# schematic.net
KiCad netlist of a schematic drawn in EasyEDA
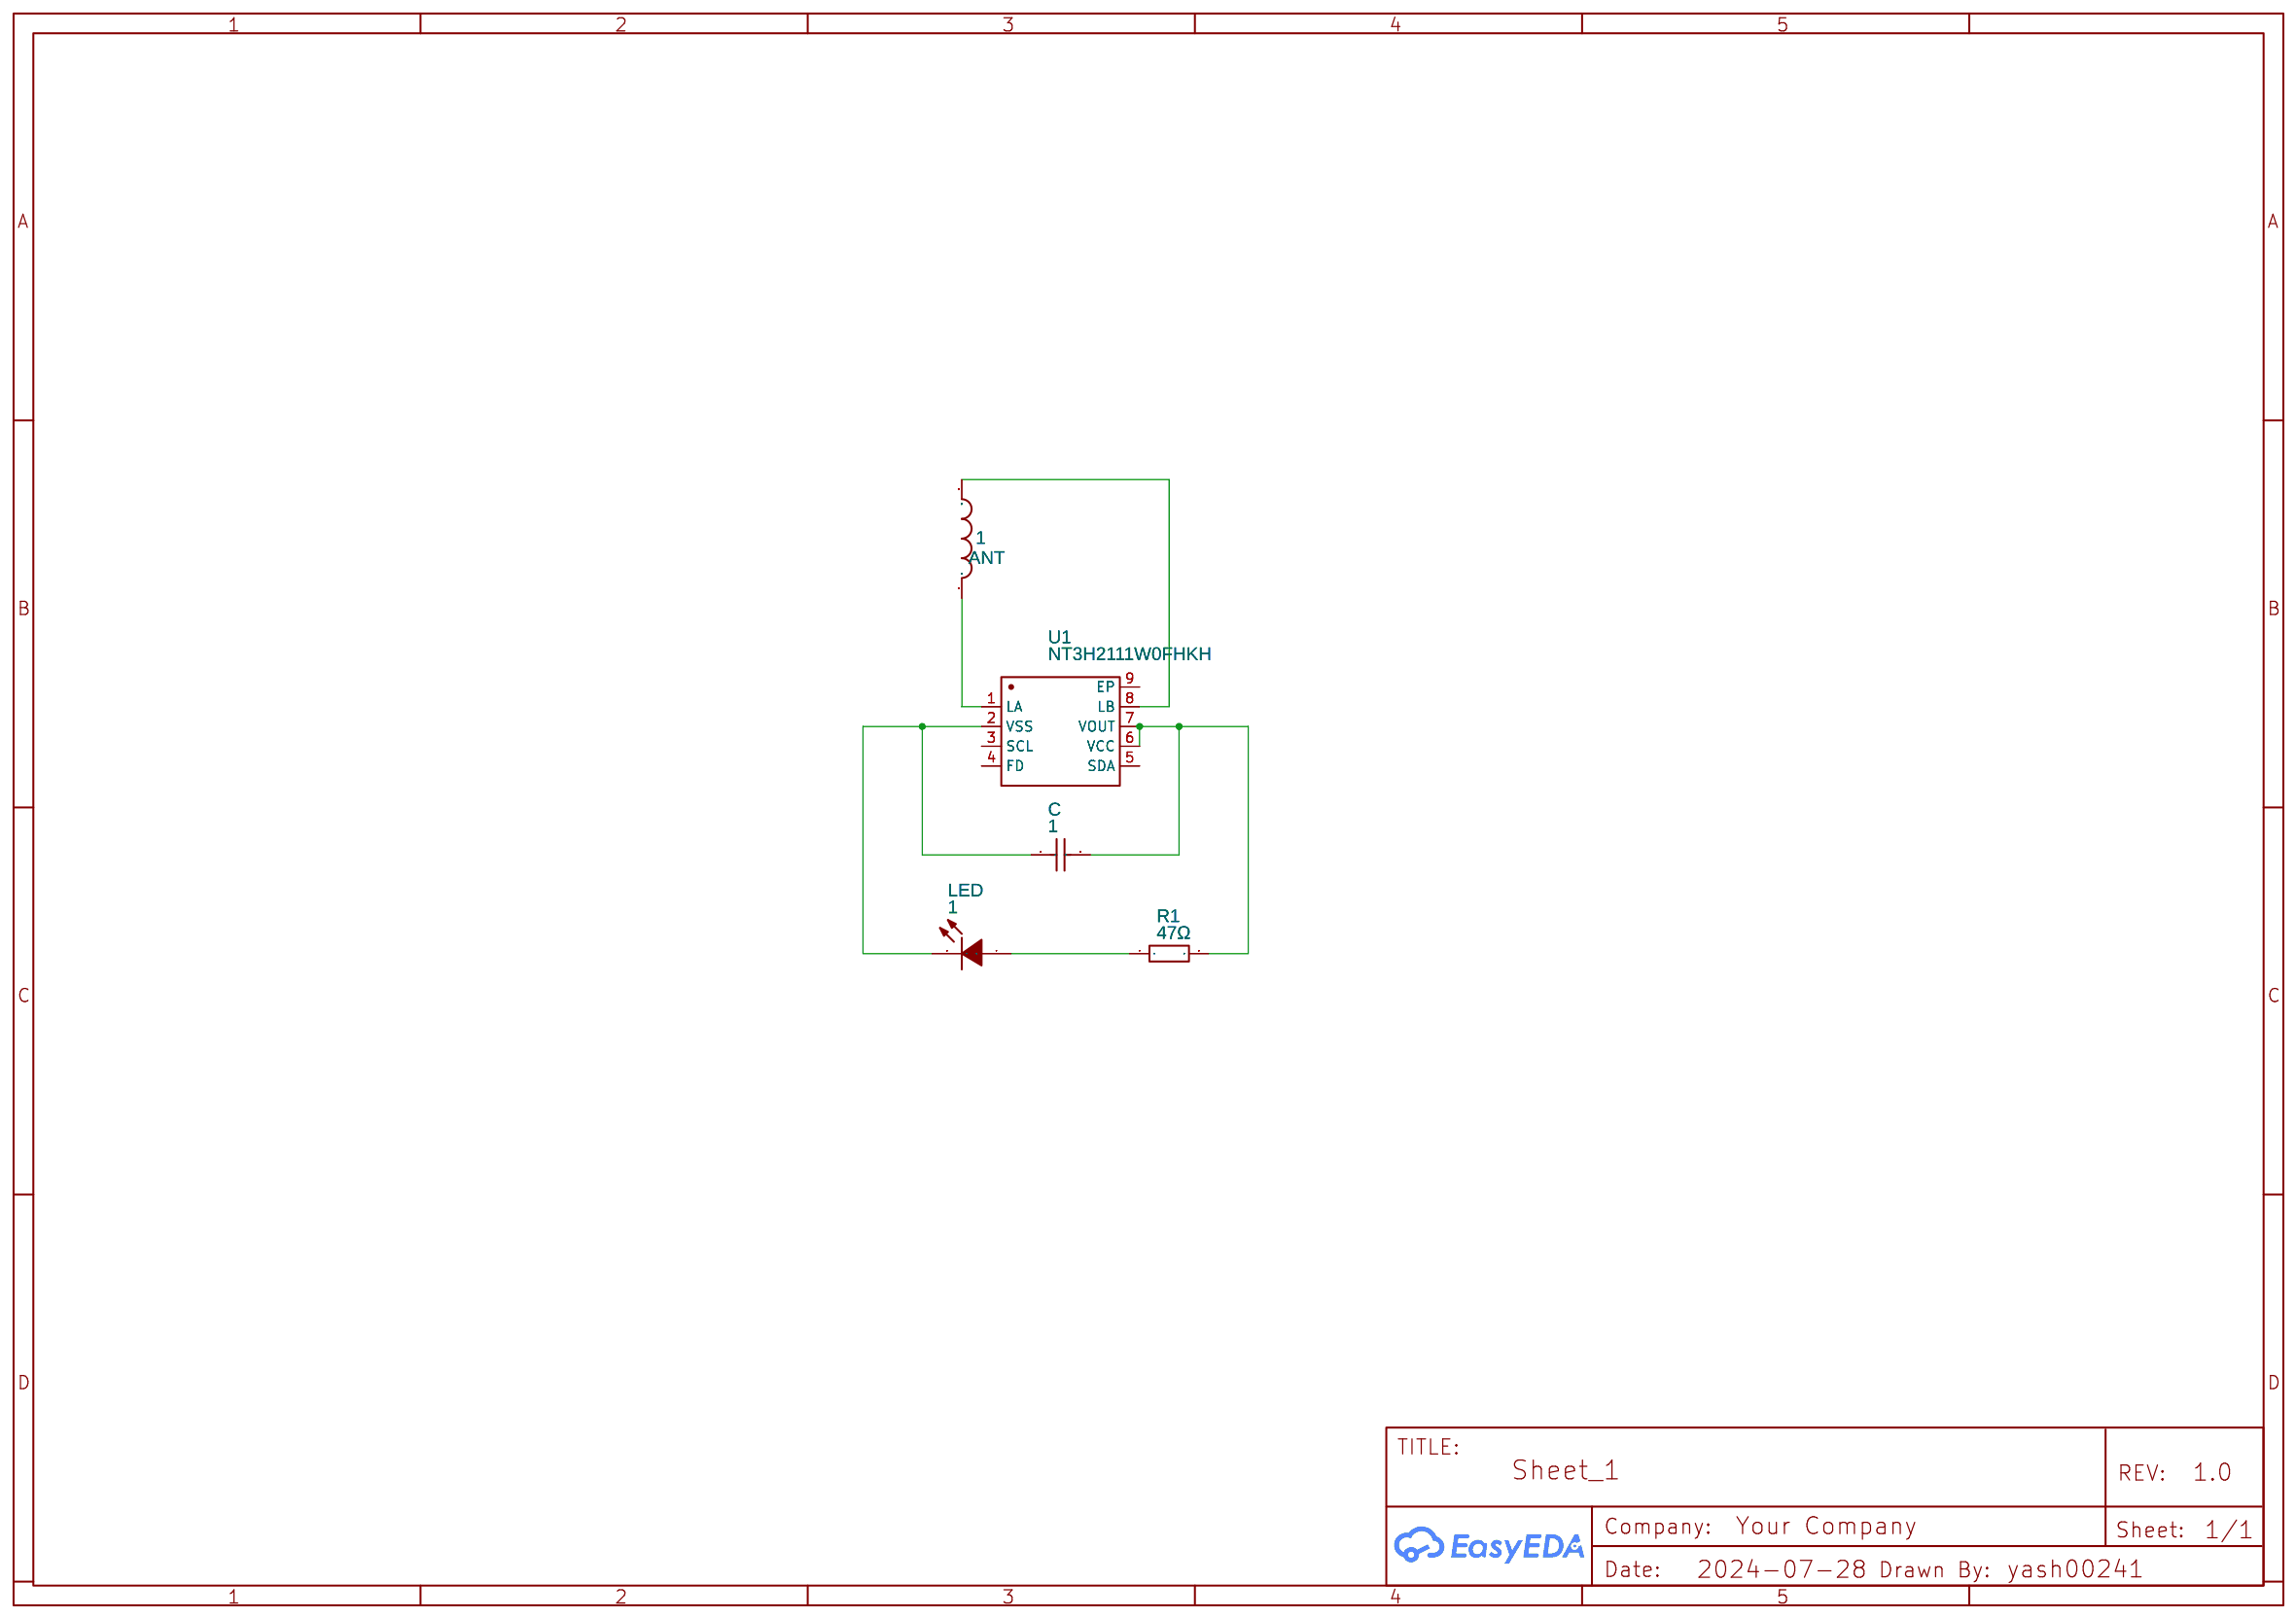
[diagram p0: schematic sheet]

(export (version "E")
  (design (tool "Eeschema 10.0.6"))
  (components
    (comp (ref "1") (value "ANT") (libsource (lib "") (part "25X48MM_NFC_ANTENNA")))
    (comp (ref "C")
      (value "1")
      (fields
        (field (name "Manufacturer Part") "CL10B224KA8NNNC")
        (field (name "Manufacturer") "SAMSUNG(三星)")
      )
      (libsource (lib "") (part "CL10B224KA8NNNC"))
    )
    (comp (ref "LED")
      (value "1")
      (fields (field (name "Manufacturer Part") "KT-0805G") (field (name "Manufacturer") "KENTO"))
      (libsource (lib "") (part "0805G (Green)"))
    )
    (comp (ref "R1")
      (value "47Ω")
      (fields
        (field (name "Manufacturer Part") "0603WAF470JT5E")
        (field (name "Manufacturer") "UNI-ROYAL(厚声)")
      )
      (libsource (lib "") (part "0603WAF470JT5E"))
    )
    (comp (ref "U1")
      (value "NT3H2111W0FHKH")
      (fields (field (name "Manufacturer") "NXP(恩智浦)"))
      (libsource (lib "") (part "NT3H2111W0FHKH"))
    )
  )
  (nets
    (net (code "1") (name "Net-(LED-A)") (class "Default")
      (node (ref "LED") (pin "1") (pinfunction "A_1") (pintype "unspecified"))
      (node (ref "R1") (pin "1") (pinfunction "1_1") (pintype "input"))
    )
    (net (code "2") (name "Net-(LED-K)") (class "Default")
      (node (ref "C") (pin "1") (pinfunction "1_1") (pintype "input"))
      (node (ref "LED") (pin "2") (pinfunction "K_2") (pintype "unspecified"))
      (node (ref "U1") (pin "2") (pinfunction "VSS_2") (pintype "unspecified"))
    )
    (net (code "3") (name "Net-(U1-LA)") (class "Default")
      (node (ref "1") (pin "P$2") (pinfunction "P$2_P$2") (pintype "bidirectional"))
      (node (ref "U1") (pin "1") (pinfunction "LA_1") (pintype "unspecified"))
    )
    (net (code "4") (name "Net-(U1-LB)") (class "Default")
      (node (ref "1") (pin "P$1") (pinfunction "P$1_P$1") (pintype "bidirectional"))
      (node (ref "U1") (pin "8") (pinfunction "LB_8") (pintype "unspecified"))
    )
    (net (code "5") (name "Net-(U1-VCC)") (class "Default")
      (node (ref "C") (pin "2") (pinfunction "2_2") (pintype "input"))
      (node (ref "R1") (pin "2") (pinfunction "2_2") (pintype "input"))
      (node (ref "U1") (pin "6") (pinfunction "VCC_6") (pintype "unspecified"))
      (node (ref "U1") (pin "7") (pinfunction "VOUT_7") (pintype "unspecified"))
    )
    (net (code "6") (name "unconnected-(U1-EP-Pad9)") (class "Default")
      (node (ref "U1") (pin "9") (pinfunction "EP_9") (pintype "unspecified"))
    )
    (net (code "7") (name "unconnected-(U1-FD-Pad4)") (class "Default")
      (node (ref "U1") (pin "4") (pinfunction "FD_4") (pintype "unspecified"))
    )
    (net (code "8") (name "unconnected-(U1-SCL-Pad3)") (class "Default")
      (node (ref "U1") (pin "3") (pinfunction "SCL_3") (pintype "unspecified"))
    )
    (net (code "9") (name "unconnected-(U1-SDA-Pad5)") (class "Default")
      (node (ref "U1") (pin "5") (pinfunction "SDA_5") (pintype "unspecified"))
    )
  )
)
